# wiz55stm32.net
KiCad netlist of a schematic drawn in Altium Designer
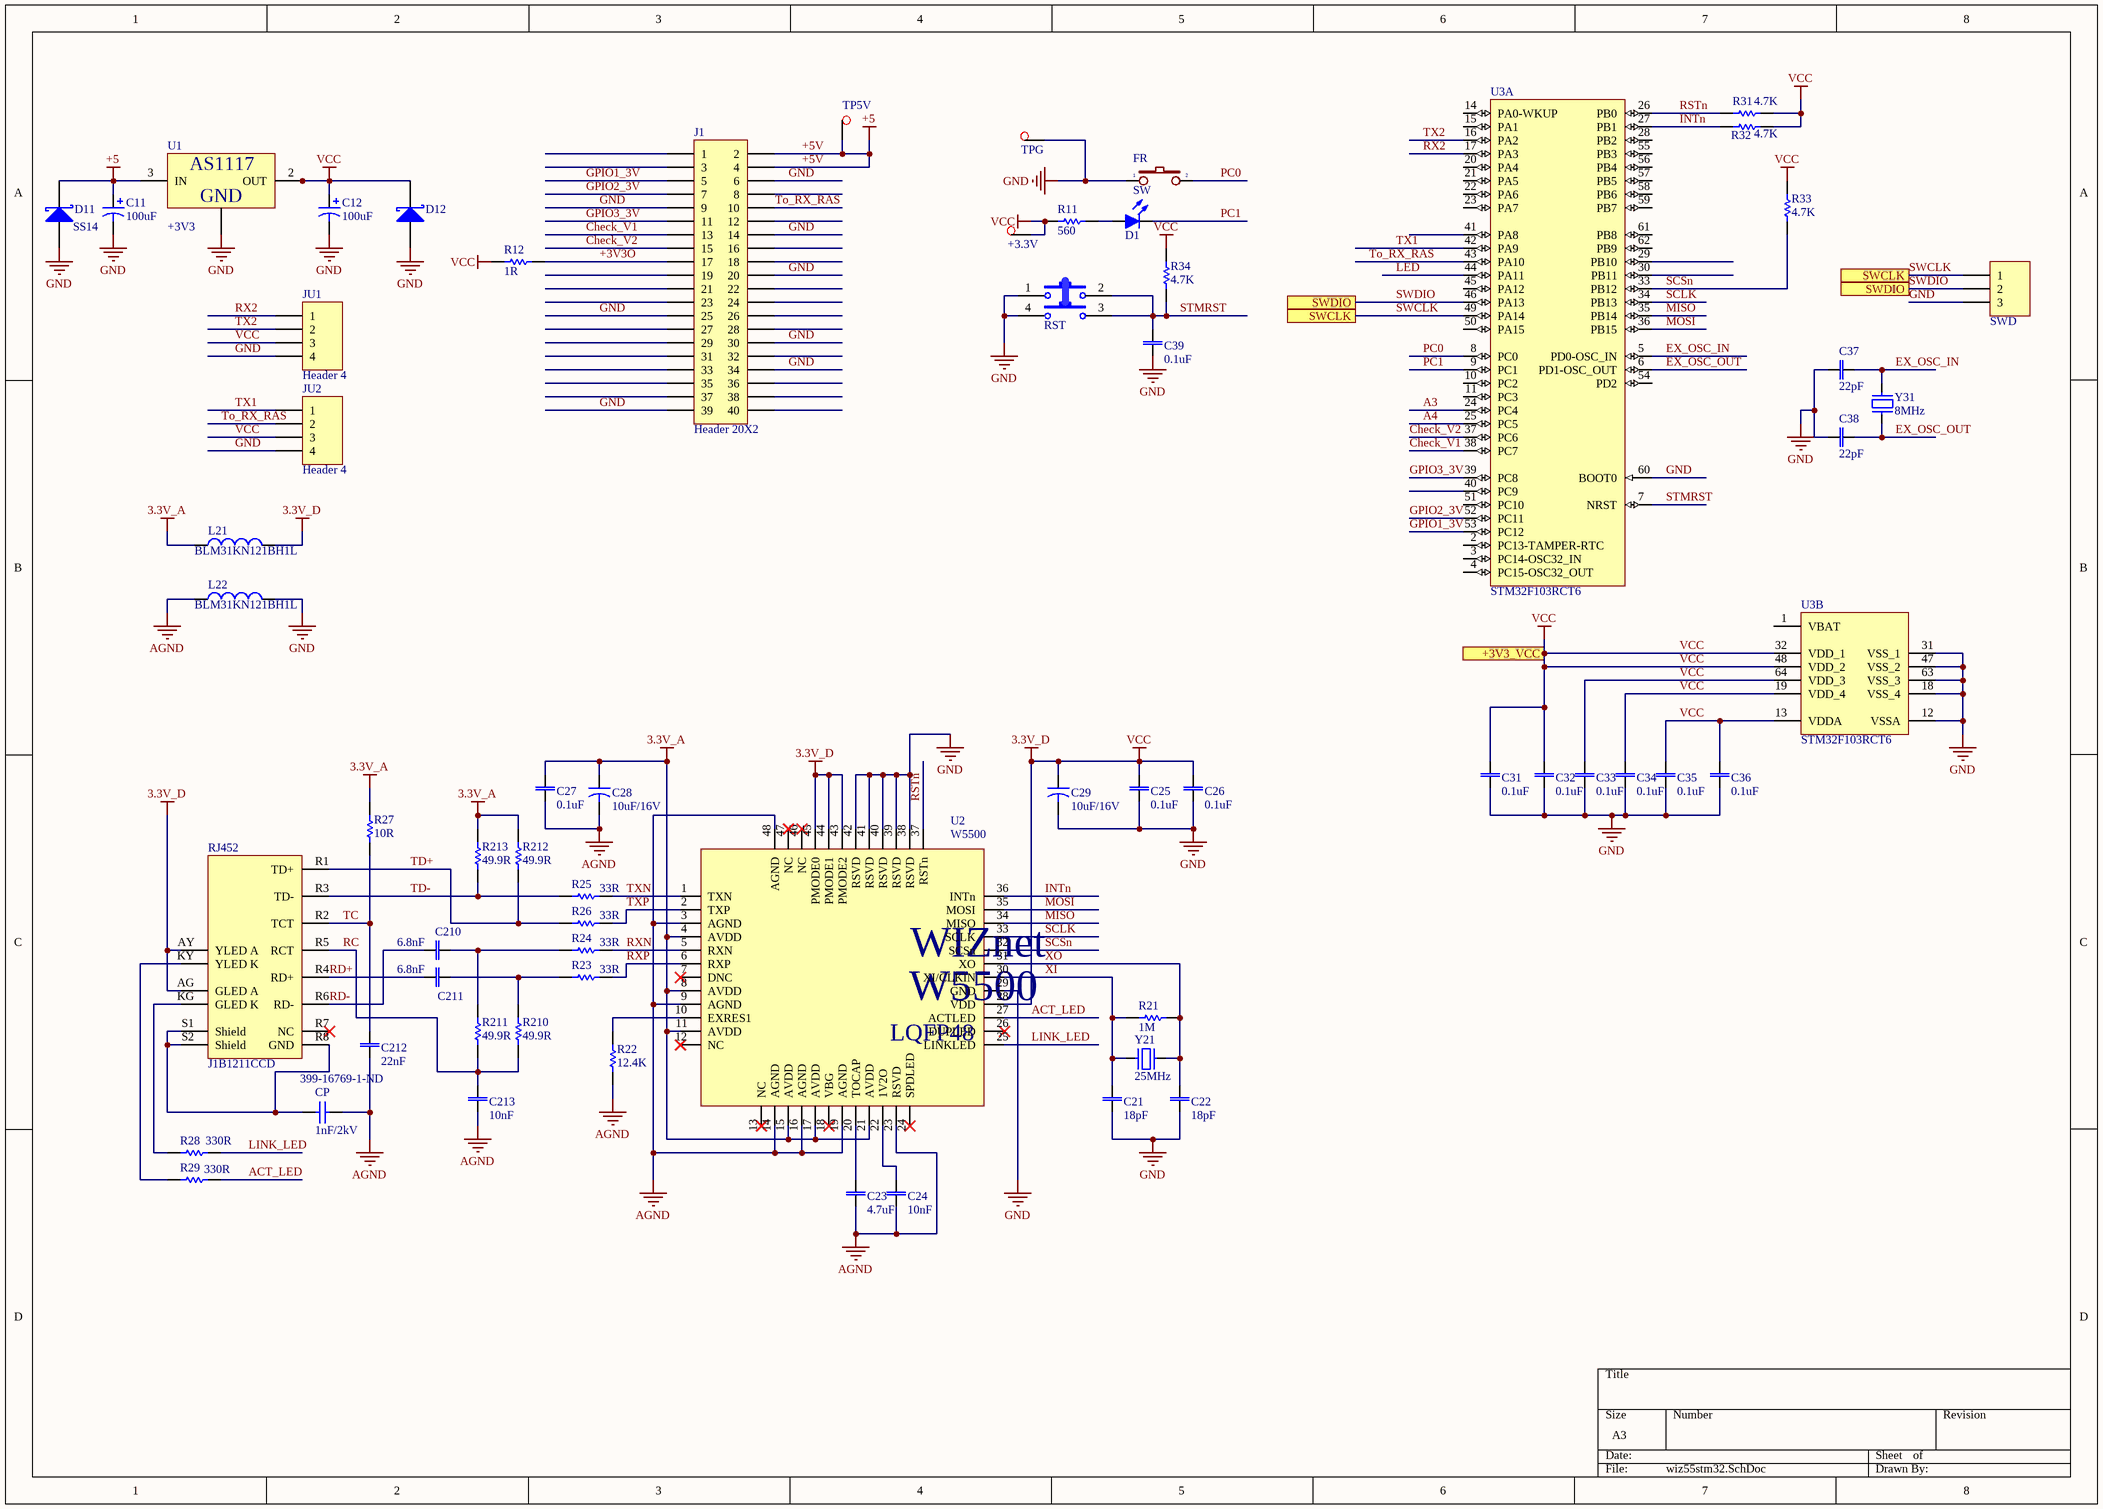
[diagram p0: wiz55stm32.SchDoc]

(export (version "E")
  (design (tool "Eeschema 10.0.6"))
  (components
    (comp (ref "+3.3V") (value "TP") (footprint "swatpcblib:TP2") (libsource (lib "swatpcblib") (part "TP")))
    (comp (ref "C11")
      (value "100uF")
      (footprint "CAP 3.8mm")
      (fields (field (name "Comment") "Cap"))
      (libsource (lib "swatpcblib") (part "Cap"))
    )
    (comp (ref "C12")
      (value "100uF")
      (footprint "CAP 3.8mm")
      (fields (field (name "Comment") "Cap"))
      (libsource (lib "swatpcblib") (part "Cap"))
    )
    (comp (ref "C21")
      (value "18pF")
      (footprint "swatpcblib:CAP 0805")
      (description "Capacitor non polarized")
      (fields (field (name "Comment") "Tụ điện dán 080518pF"))
      (libsource (lib "swatpcblib") (part "CAP NP"))
    )
    (comp (ref "C22")
      (value "18pF")
      (footprint "swatpcblib:CAP 0805")
      (description "Capacitor non polarized")
      (fields (field (name "Comment") "Tụ điện dán 080518pF"))
      (libsource (lib "swatpcblib") (part "CAP NP"))
    )
    (comp (ref "C23")
      (value "4.7uF")
      (footprint "swatpcblib:CAP 0805")
      (description "Capacitor non polarized")
      (fields (field (name "Comment") "Tụ điện dán 08054.7uF"))
      (libsource (lib "swatpcblib") (part "CAP NP"))
    )
    (comp (ref "C24")
      (value "10nF")
      (footprint "swatpcblib:CAP 0805")
      (description "Capacitor non polarized")
      (fields (field (name "Comment") "Tụ điện dán 080510nF"))
      (libsource (lib "swatpcblib") (part "CAP NP"))
    )
    (comp (ref "C25")
      (value "0.1uF")
      (footprint "swatpcblib:CAP 0805")
      (description "Capacitor non polarized")
      (fields (field (name "Comment") "Tụ điện dán 08050.1uF"))
      (libsource (lib "swatpcblib") (part "CAP NP"))
    )
    (comp (ref "C26")
      (value "0.1uF")
      (footprint "swatpcblib:CAP 0805")
      (description "Capacitor non polarized")
      (fields (field (name "Comment") "Tụ điện dán 08050.1uF"))
      (libsource (lib "swatpcblib") (part "CAP NP"))
    )
    (comp (ref "C27")
      (value "0.1uF")
      (footprint "swatpcblib:CAP 0805")
      (description "Capacitor non polarized")
      (fields (field (name "Comment") "Tụ điện dán 08050.1uF"))
      (libsource (lib "swatpcblib") (part "CAP NP"))
    )
    (comp (ref "C28")
      (value "10uF/16V")
      (footprint "CAP-A Size")
      (description "Tantla CAP A Size EIA/IECQ 3216")
      (libsource (lib "Scott_lib") (part "CAP-A Size"))
    )
    (comp (ref "C29")
      (value "10uF/16V")
      (footprint "CAP-A Size")
      (description "Tantla CAP A Size EIA/IECQ 3216")
      (libsource (lib "Scott_lib") (part "CAP-A Size"))
    )
    (comp (ref "C31")
      (value "0.1uF")
      (footprint "swatpcblib:CAP 0805")
      (description "Capacitor non polarized")
      (fields (field (name "Comment") "Tụ điện dán 08050.1uF"))
      (libsource (lib "swatpcblib") (part "CAP NP"))
    )
    (comp (ref "C32")
      (value "0.1uF")
      (footprint "swatpcblib:CAP 0805")
      (description "Capacitor non polarized")
      (fields (field (name "Comment") "Tụ điện dán 08050.1uF"))
      (libsource (lib "swatpcblib") (part "CAP NP"))
    )
    (comp (ref "C33")
      (value "0.1uF")
      (footprint "swatpcblib:CAP 0805")
      (description "Capacitor non polarized")
      (fields (field (name "Comment") "Tụ điện dán 08050.1uF"))
      (libsource (lib "swatpcblib") (part "CAP NP"))
    )
    (comp (ref "C34")
      (value "0.1uF")
      (footprint "swatpcblib:CAP 0805")
      (description "Capacitor non polarized")
      (fields (field (name "Comment") "Tụ điện dán 08050.1uF"))
      (libsource (lib "swatpcblib") (part "CAP NP"))
    )
    (comp (ref "C35")
      (value "0.1uF")
      (footprint "swatpcblib:CAP 0805")
      (description "Capacitor non polarized")
      (fields (field (name "Comment") "Tụ điện dán 08050.1uF"))
      (libsource (lib "swatpcblib") (part "CAP NP"))
    )
    (comp (ref "C36")
      (value "0.1uF")
      (footprint "swatpcblib:CAP 0805")
      (description "Capacitor non polarized")
      (fields (field (name "Comment") "Tụ điện dán 08050.1uF"))
      (libsource (lib "swatpcblib") (part "CAP NP"))
    )
    (comp (ref "C37")
      (value "22pF")
      (footprint "swatpcblib:CAP 0805")
      (description "Capacitor non polarized")
      (fields (field (name "Comment") "Tụ điện dán 080522pF"))
      (libsource (lib "swatpcblib") (part "CAP NP"))
    )
    (comp (ref "C38")
      (value "22pF")
      (footprint "swatpcblib:CAP 0805")
      (description "Capacitor non polarized")
      (fields (field (name "Comment") "Tụ điện dán 080522pF"))
      (libsource (lib "swatpcblib") (part "CAP NP"))
    )
    (comp (ref "C39")
      (value "0.1uF")
      (footprint "swatpcblib:CAP 0805")
      (description "Capacitor non polarized")
      (fields (field (name "Comment") "Tụ điện dán 08050.1uF"))
      (libsource (lib "swatpcblib") (part "CAP NP"))
    )
    (comp (ref "C210")
      (value "6.8nF")
      (footprint "swatpcblib:CAP 0805")
      (description "Capacitor non polarized")
      (fields (field (name "Comment") "Tụ điện dán 08056.8nF"))
      (libsource (lib "swatpcblib") (part "CAP NP"))
    )
    (comp (ref "C211")
      (value "6.8nF")
      (footprint "swatpcblib:CAP 0805")
      (description "Capacitor non polarized")
      (fields (field (name "Comment") "Tụ điện dán 08056.8nF"))
      (libsource (lib "swatpcblib") (part "CAP NP"))
    )
    (comp (ref "C212")
      (value "22nF")
      (footprint "swatpcblib:CAP 0805")
      (description "Capacitor non polarized")
      (fields (field (name "Comment") "Tụ điện dán 080522nF"))
      (libsource (lib "swatpcblib") (part "CAP NP"))
    )
    (comp (ref "C213")
      (value "10nF")
      (footprint "swatpcblib:CAP 0805")
      (description "Capacitor non polarized")
      (fields (field (name "Comment") "Tụ điện dán 080510nF"))
      (libsource (lib "swatpcblib") (part "CAP NP"))
    )
    (comp (ref "CP")
      (value "1nF/2kV")
      (footprint "CAP-1808")
      (description "Ceramic CAP 1808(4520)")
      (fields (field (name "SUPPLIER PART NUMBER 1") "399-16769-1-ND") (field (name "TOLERANCE") "20%"))
      (libsource (lib "Scott_lib") (part "CAP-1808"))
    )
    (comp (ref "D1") (value "Led") (footprint "LED 5mm Green") (libsource (lib "swatpcblib") (part "Led")))
    (comp (ref "D11")
      (value "SS14")
      (footprint "PBL - SMD Packages:DO-214AC")
      (description "Schottky Diodes Through Hole 3 A 40 V Schottky Diodes, DO-201AD, SB340 ,MBR340")
      (fields (field (name "Comment") "Đi ốt dánSS14"))
      (libsource (lib "swatpcblib") (part "Diodes Schottky"))
    )
    (comp (ref "D12")
      (value "Đi ốt dánPN:CPDH3V3UP")
      (footprint "swatpcblib:DO-35")
      (description "Zener 3.3V/1W")
      (libsource (lib "swatpcblib") (part "Diodes Schottky"))
    )
    (comp (ref "FR")
      (value "SW")
      (footprint "heromap:SW2-D1")
      (description "Switch button 2 pin")
      (libsource (lib "heromap") (part "SW2"))
    )
    (comp (ref "J1")
      (value "Header 20X2")
      (footprint "HDR2X20")
      (description "Header, 20-Pin, Dual row")
      (fields (field (name "PUBLISHER") "Altium Limited"))
      (libsource (lib "Miscellaneous Connectors") (part "Header 20X2"))
    )
    (comp (ref "JU1")
      (value "Header 4")
      (footprint "heromap:HDR1X4")
      (description "Header, 4-Pin")
      (fields (field (name "PUBLISHER") "Altium Limited"))
      (libsource (lib "heromap") (part "Header 4"))
    )
    (comp (ref "JU2")
      (value "Header 4")
      (footprint "heromap:HDR1X4")
      (description "Header, 4-Pin")
      (fields (field (name "PUBLISHER") "Altium Limited"))
      (libsource (lib "heromap") (part "Header 4"))
    )
    (comp (ref "L21")
      (value "BLM31KN121BH1L")
      (footprint "swatpcblib:SMD 1206")
      (description "Ferrite Beads 1206 120ohms 4A AEC-Q200")
      (libsource (lib "Scott_lib") (part "IND-0603"))
    )
    (comp (ref "L22")
      (value "BLM31KN121BH1L")
      (footprint "swatpcblib:SMD 1206")
      (description "Ferrite Beads 1206 120ohms 4A AEC-Q200")
      (libsource (lib "Scott_lib") (part "IND-0603"))
    )
    (comp (ref "R11")
      (value "560")
      (footprint "swatpcblib:RES 0805")
      (description "Resistor")
      (fields (field (name "Comment") "Điện trở dán 0603560"))
      (libsource (lib "swatpcblib") (part "Res"))
    )
    (comp (ref "R12")
      (value "1R")
      (footprint "swatpcblib:RES 0805")
      (description "Resistor")
      (fields (field (name "Comment") "Điện trở dán 08051R"))
      (libsource (lib "swatpcblib") (part "Res"))
    )
    (comp (ref "R21")
      (value "1M")
      (footprint "swatpcblib:RES 0805")
      (description "Resistor")
      (fields (field (name "Comment") "Điện trở dán 08051M"))
      (libsource (lib "swatpcblib") (part "Res"))
    )
    (comp (ref "R22")
      (value "12.4K")
      (footprint "swatpcblib:RES 0805")
      (description "Resistor")
      (fields (field (name "Comment") "Điện trở dán 080512.4K"))
      (libsource (lib "swatpcblib") (part "Res"))
    )
    (comp (ref "R23")
      (value "33R")
      (footprint "swatpcblib:RES 0805")
      (description "Resistor")
      (fields (field (name "Comment") "Điện trở dán 080533R"))
      (libsource (lib "swatpcblib") (part "Res"))
    )
    (comp (ref "R24")
      (value "33R")
      (footprint "swatpcblib:RES 0805")
      (description "Resistor")
      (fields (field (name "Comment") "Điện trở dán 080533R"))
      (libsource (lib "swatpcblib") (part "Res"))
    )
    (comp (ref "R25")
      (value "33R")
      (footprint "swatpcblib:RES 0805")
      (description "Resistor")
      (fields (field (name "Comment") "Điện trở dán 080533R"))
      (libsource (lib "swatpcblib") (part "Res"))
    )
    (comp (ref "R26")
      (value "33R")
      (footprint "swatpcblib:RES 0805")
      (description "Resistor")
      (fields (field (name "Comment") "Điện trở dán 080533R"))
      (libsource (lib "swatpcblib") (part "Res"))
    )
    (comp (ref "R27")
      (value "10R")
      (footprint "swatpcblib:RES 0805")
      (description "Resistor")
      (fields (field (name "Comment") "Điện trở dán 080510R"))
      (libsource (lib "swatpcblib") (part "Res"))
    )
    (comp (ref "R28")
      (value "330R")
      (footprint "swatpcblib:RES 0805")
      (description "Resistor")
      (fields (field (name "Comment") "Điện trở dán 0805330R"))
      (libsource (lib "swatpcblib") (part "Res"))
    )
    (comp (ref "R29")
      (value "330R")
      (footprint "swatpcblib:RES 0805")
      (description "Resistor")
      (fields (field (name "Comment") "Điện trở dán 0805330R"))
      (libsource (lib "swatpcblib") (part "Res"))
    )
    (comp (ref "R31")
      (value "4.7K")
      (footprint "swatpcblib:RES 0805")
      (description "Resistor")
      (fields (field (name "Comment") "Điện trở dán 08054.7K"))
      (libsource (lib "swatpcblib") (part "Res"))
    )
    (comp (ref "R32")
      (value "4.7K")
      (footprint "swatpcblib:RES 0805")
      (description "Resistor")
      (fields (field (name "Comment") "Điện trở dán 08054.7K"))
      (libsource (lib "swatpcblib") (part "Res"))
    )
    (comp (ref "R33")
      (value "4.7K")
      (footprint "swatpcblib:RES 0805")
      (description "Resistor")
      (fields (field (name "Comment") "Điện trở dán 08054.7K"))
      (libsource (lib "swatpcblib") (part "Res"))
    )
    (comp (ref "R34")
      (value "4.7K")
      (footprint "swatpcblib:RES 0805")
      (description "Resistor")
      (fields (field (name "Comment") "Điện trở dán 08054.7K"))
      (libsource (lib "swatpcblib") (part "Res"))
    )
    (comp (ref "R210")
      (value "49.9R")
      (footprint "swatpcblib:RES 0805")
      (description "Resistor")
      (fields (field (name "Comment") "Điện trở dán 080549.9R"))
      (libsource (lib "swatpcblib") (part "Res"))
    )
    (comp (ref "R211")
      (value "49.9R")
      (footprint "swatpcblib:RES 0805")
      (description "Resistor")
      (fields (field (name "Comment") "Điện trở dán 080549.9R"))
      (libsource (lib "swatpcblib") (part "Res"))
    )
    (comp (ref "R212")
      (value "49.9R")
      (footprint "swatpcblib:RES 0805")
      (description "Resistor")
      (fields (field (name "Comment") "Điện trở dán 080549.9R"))
      (libsource (lib "swatpcblib") (part "Res"))
    )
    (comp (ref "R213")
      (value "49.9R")
      (footprint "swatpcblib:RES 0805")
      (description "Resistor")
      (fields (field (name "Comment") "Điện trở dán 080549.9R"))
      (libsource (lib "swatpcblib") (part "Res"))
    )
    (comp (ref "RJ452")
      (value "J1B1211CCD")
      (footprint "swatpcblib:J1B1211CCD")
      (libsource (lib "WIZ850io_SCH_V100") (part "BS-R250210"))
    )
    (comp (ref "RST")
      (value "Nút bấm 4 chân cắm12x12x6mm")
      (footprint "SW")
      (libsource (lib "swatpcblib") (part "SW-4P-Small"))
    )
    (comp (ref "SWD")
      (value "Header 3")
      (footprint "heromap:HDR1X3")
      (description "Header, 3-Pin")
      (fields (field (name "PUBLISHER") "Altium Limited"))
      (libsource (lib "heromap") (part "Header 3"))
    )
    (comp (ref "TP5V") (value "TP") (footprint "swatpcblib:TP2") (libsource (lib "swatpcblib") (part "TP")))
    (comp (ref "TPG") (value "TP") (footprint "swatpcblib:TP2") (libsource (lib "swatpcblib") (part "TP")))
    (comp (ref "U1")
      (value "IC nguồn AS1117 dán+3V3")
      (footprint "SOT223-4N")
      (fields (field (name "VL") "+3V3"))
      (libsource (lib "swatpcblib") (part "AS1117"))
    )
    (comp (ref "U2")
      (value "W5500")
      (footprint "swatpcblib:WIZNET W5500")
      (description "WIZnet W5500")
      (libsource (lib "WIZnet Open-source Hardware Library V1.0") (part "W5500"))
    )
    (comp (ref "U3")
      (value "STM32F103RCT6")
      (footprint "LQFP64_Tuan")
      (libsource (lib "STMicroelectronics STM32 F1") (part "STM32F103RCT6"))
    )
    (comp (ref "Y21") (value "25MHz") (footprint "XT2") (libsource (lib "swatpcblib") (part "Crystal")))
    (comp (ref "Y31") (value "8MHz") (footprint "XT2") (libsource (lib "Tuan") (part "Crystal")))
  )
  (nets
    (net (code "1") (name "+5") (class "Default")
      (node (ref "C11") (pin "1") (pinfunction "1_1") (pintype "passive"))
      (node (ref "D11") (pin "K") (pinfunction "K_K") (pintype "passive"))
      (node (ref "J1") (pin "2") (pinfunction "2_2") (pintype "passive"))
      (node (ref "J1") (pin "4") (pinfunction "4_4") (pintype "passive"))
      (node (ref "TP5V") (pin "1") (pinfunction "1_1") (pintype "passive"))
      (node (ref "U1") (pin "3") (pinfunction "IN_3") (pintype "power_in"))
    )
    (net (code "2") (name "/+3V3O") (class "Default")
      (node (ref "J1") (pin "17") (pinfunction "17_17") (pintype "passive"))
      (node (ref "R12") (pin "2") (pinfunction "2_2") (pintype "passive"))
    )
    (net (code "3") (name "/A3") (class "Default")
      (node (ref "U3") (pin "24") (pinfunction "PC4_24") (pintype "bidirectional"))
    )
    (net (code "4") (name "/A4") (class "Default")
      (node (ref "U3") (pin "25") (pinfunction "PC5_25") (pintype "bidirectional"))
    )
    (net (code "5") (name "/ACT_LED") (class "Default")
      (node (ref "R29") (pin "2") (pinfunction "2_2") (pintype "passive"))
      (node (ref "U2") (pin "27") (pinfunction "ACTLED_27") (pintype "passive"))
    )
    (net (code "6") (name "/Check_V1") (class "Default")
      (node (ref "J1") (pin "13") (pinfunction "13_13") (pintype "passive"))
      (node (ref "U3") (pin "38") (pinfunction "PC7_38") (pintype "bidirectional"))
    )
    (net (code "7") (name "/Check_V2") (class "Default")
      (node (ref "J1") (pin "15") (pinfunction "15_15") (pintype "passive"))
      (node (ref "U3") (pin "37") (pinfunction "PC6_37") (pintype "bidirectional"))
    )
    (net (code "8") (name "/EX_OSC_IN") (class "Default")
      (node (ref "C37") (pin "1") (pinfunction "1_1") (pintype "passive"))
      (node (ref "U3") (pin "5") (pinfunction "PD0-OSC_IN_5") (pintype "bidirectional"))
      (node (ref "Y31") (pin "2") (pinfunction "2_2") (pintype "passive"))
    )
    (net (code "9") (name "/EX_OSC_OUT") (class "Default")
      (node (ref "C38") (pin "1") (pinfunction "1_1") (pintype "passive"))
      (node (ref "U3") (pin "6") (pinfunction "PD1-OSC_OUT_6") (pintype "bidirectional"))
      (node (ref "Y31") (pin "1") (pinfunction "1_1") (pintype "passive"))
    )
    (net (code "10") (name "/GPIO1_3V") (class "Default")
      (node (ref "J1") (pin "5") (pinfunction "5_5") (pintype "passive"))
      (node (ref "U3") (pin "53") (pinfunction "PC12_53") (pintype "bidirectional"))
    )
    (net (code "11") (name "/GPIO2_3V") (class "Default")
      (node (ref "J1") (pin "7") (pinfunction "7_7") (pintype "passive"))
      (node (ref "U3") (pin "52") (pinfunction "PC11_52") (pintype "bidirectional"))
    )
    (net (code "12") (name "/GPIO3_3V") (class "Default")
      (node (ref "J1") (pin "11") (pinfunction "11_11") (pintype "passive"))
      (node (ref "U3") (pin "39") (pinfunction "PC8_39") (pintype "bidirectional"))
    )
    (net (code "13") (name "/INTn") (class "Default")
      (node (ref "R32") (pin "2") (pinfunction "2_2") (pintype "passive"))
      (node (ref "U2") (pin "36") (pinfunction "INTn_36") (pintype "passive"))
      (node (ref "U3") (pin "27") (pinfunction "PB1_27") (pintype "bidirectional"))
    )
    (net (code "14") (name "/LED") (class "Default")
      (node (ref "U3") (pin "44") (pinfunction "PA11_44") (pintype "bidirectional"))
    )
    (net (code "15") (name "/LINK_LED") (class "Default")
      (node (ref "R28") (pin "2") (pinfunction "2_2") (pintype "passive"))
      (node (ref "U2") (pin "25") (pinfunction "LINKLED_25") (pintype "passive"))
    )
    (net (code "16") (name "/MISO") (class "Default")
      (node (ref "U2") (pin "34") (pinfunction "MISO_34") (pintype "passive"))
      (node (ref "U3") (pin "35") (pinfunction "PB14_35") (pintype "bidirectional"))
    )
    (net (code "17") (name "/MOSI") (class "Default")
      (node (ref "U2") (pin "35") (pinfunction "MOSI_35") (pintype "passive"))
      (node (ref "U3") (pin "36") (pinfunction "PB15_36") (pintype "bidirectional"))
    )
    (net (code "18") (name "/PC0") (class "Default")
      (node (ref "FR") (pin "2") (pinfunction "2_2") (pintype "passive"))
      (node (ref "U3") (pin "8") (pinfunction "PC0_8") (pintype "bidirectional"))
    )
    (net (code "19") (name "/PC1") (class "Default")
      (node (ref "D1") (pin "K") (pinfunction "K_K") (pintype "passive"))
      (node (ref "U3") (pin "9") (pinfunction "PC1_9") (pintype "bidirectional"))
    )
    (net (code "20") (name "/RC") (class "Default")
      (node (ref "C213") (pin "1") (pinfunction "1_1") (pintype "passive"))
      (node (ref "R210") (pin "1") (pinfunction "1_1") (pintype "passive"))
      (node (ref "R211") (pin "1") (pinfunction "1_1") (pintype "passive"))
      (node (ref "RJ452") (pin "R5") (pinfunction "RCT_R5") (pintype "passive"))
    )
    (net (code "21") (name "/RD+") (class "Default")
      (node (ref "C211") (pin "2") (pinfunction "2_2") (pintype "passive"))
      (node (ref "RJ452") (pin "R4") (pinfunction "RD+_R4") (pintype "passive"))
    )
    (net (code "22") (name "/RD-") (class "Default")
      (node (ref "C210") (pin "2") (pinfunction "2_2") (pintype "passive"))
      (node (ref "RJ452") (pin "R6") (pinfunction "RD-_R6") (pintype "passive"))
    )
    (net (code "23") (name "/RSTn") (class "Default")
      (node (ref "R31") (pin "2") (pinfunction "2_2") (pintype "passive"))
      (node (ref "U2") (pin "37") (pinfunction "RSTn_37") (pintype "passive"))
      (node (ref "U3") (pin "26") (pinfunction "PB0_26") (pintype "bidirectional"))
    )
    (net (code "24") (name "/RX2") (class "Default")
      (node (ref "JU1") (pin "1") (pinfunction "1_1") (pintype "passive"))
      (node (ref "U3") (pin "17") (pinfunction "PA3_17") (pintype "bidirectional"))
    )
    (net (code "25") (name "/RXN") (class "Default")
      (node (ref "R24") (pin "1") (pinfunction "1_1") (pintype "passive"))
      (node (ref "U2") (pin "5") (pinfunction "RXN_5") (pintype "passive"))
    )
    (net (code "26") (name "/RXP") (class "Default")
      (node (ref "R23") (pin "1") (pinfunction "1_1") (pintype "passive"))
      (node (ref "U2") (pin "6") (pinfunction "RXP_6") (pintype "passive"))
    )
    (net (code "27") (name "/SCLK") (class "Default")
      (node (ref "U2") (pin "33") (pinfunction "SCLK_33") (pintype "passive"))
      (node (ref "U3") (pin "34") (pinfunction "PB13_34") (pintype "bidirectional"))
    )
    (net (code "28") (name "/SCSn") (class "Default")
      (node (ref "R33") (pin "1") (pinfunction "1_1") (pintype "passive"))
      (node (ref "U2") (pin "32") (pinfunction "SCSn_32") (pintype "passive"))
      (node (ref "U3") (pin "33") (pinfunction "PB12_33") (pintype "bidirectional"))
    )
    (net (code "29") (name "/STMRST") (class "Default")
      (node (ref "C39") (pin "2") (pinfunction "2_2") (pintype "passive"))
      (node (ref "R34") (pin "1") (pinfunction "1_1") (pintype "passive"))
      (node (ref "RST") (pin "2") (pinfunction "2_2") (pintype "passive"))
      (node (ref "RST") (pin "3") (pinfunction "3_3") (pintype "passive"))
      (node (ref "U3") (pin "7") (pinfunction "NRST_7") (pintype "bidirectional"))
    )
    (net (code "30") (name "/SWCLK") (class "Default")
      (node (ref "SWD") (pin "1") (pinfunction "1_1") (pintype "passive"))
      (node (ref "U3") (pin "49") (pinfunction "PA14_49") (pintype "bidirectional"))
    )
    (net (code "31") (name "/SWDIO") (class "Default")
      (node (ref "SWD") (pin "2") (pinfunction "2_2") (pintype "passive"))
      (node (ref "U3") (pin "46") (pinfunction "PA13_46") (pintype "bidirectional"))
    )
    (net (code "32") (name "/TC") (class "Default")
      (node (ref "C212") (pin "1") (pinfunction "1_1") (pintype "passive"))
      (node (ref "R27") (pin "2") (pinfunction "2_2") (pintype "passive"))
      (node (ref "RJ452") (pin "R2") (pinfunction "TCT_R2") (pintype "passive"))
    )
    (net (code "33") (name "/TD+") (class "Default")
      (node (ref "R212") (pin "1") (pinfunction "1_1") (pintype "passive"))
      (node (ref "R26") (pin "2") (pinfunction "2_2") (pintype "passive"))
      (node (ref "RJ452") (pin "R1") (pinfunction "TD+_R1") (pintype "passive"))
    )
    (net (code "34") (name "/TD-") (class "Default")
      (node (ref "R213") (pin "1") (pinfunction "1_1") (pintype "passive"))
      (node (ref "R25") (pin "2") (pinfunction "2_2") (pintype "passive"))
      (node (ref "RJ452") (pin "R3") (pinfunction "TD-_R3") (pintype "passive"))
    )
    (net (code "35") (name "/TX1") (class "Default")
      (node (ref "JU2") (pin "1") (pinfunction "1_1") (pintype "passive"))
      (node (ref "U3") (pin "42") (pinfunction "PA9_42") (pintype "bidirectional"))
    )
    (net (code "36") (name "/TX2") (class "Default")
      (node (ref "JU1") (pin "2") (pinfunction "2_2") (pintype "passive"))
      (node (ref "U3") (pin "16") (pinfunction "PA2_16") (pintype "bidirectional"))
    )
    (net (code "37") (name "/TXN") (class "Default")
      (node (ref "R25") (pin "1") (pinfunction "1_1") (pintype "passive"))
      (node (ref "U2") (pin "1") (pinfunction "TXN_1") (pintype "passive"))
    )
    (net (code "38") (name "/TXP") (class "Default")
      (node (ref "R26") (pin "1") (pinfunction "1_1") (pintype "passive"))
      (node (ref "U2") (pin "2") (pinfunction "TXP_2") (pintype "passive"))
    )
    (net (code "39") (name "/To_RX_RAS") (class "Default")
      (node (ref "J1") (pin "10") (pinfunction "10_10") (pintype "passive"))
      (node (ref "JU2") (pin "2") (pinfunction "2_2") (pintype "passive"))
      (node (ref "U3") (pin "43") (pinfunction "PA10_43") (pintype "bidirectional"))
    )
    (net (code "40") (name "/XI") (class "Default")
      (node (ref "C21") (pin "2") (pinfunction "2_2") (pintype "passive"))
      (node (ref "R21") (pin "1") (pinfunction "1_1") (pintype "passive"))
      (node (ref "U2") (pin "30") (pinfunction "XI/CLKIN_30") (pintype "passive"))
      (node (ref "Y21") (pin "1") (pinfunction "1_1") (pintype "passive"))
    )
    (net (code "41") (name "/XO") (class "Default")
      (node (ref "C22") (pin "2") (pinfunction "2_2") (pintype "passive"))
      (node (ref "R21") (pin "2") (pinfunction "2_2") (pintype "passive"))
      (node (ref "U2") (pin "31") (pinfunction "XO_31") (pintype "passive"))
      (node (ref "Y21") (pin "2") (pinfunction "2_2") (pintype "passive"))
    )
    (net (code "42") (name "3.3V_A") (class "Default")
      (node (ref "C27") (pin "2") (pinfunction "2_2") (pintype "passive"))
      (node (ref "C28") (pin "1") (pinfunction "1_1") (pintype "passive"))
      (node (ref "L21") (pin "1") (pinfunction "1_1") (pintype "passive"))
      (node (ref "R212") (pin "2") (pinfunction "2_2") (pintype "passive"))
      (node (ref "R213") (pin "2") (pinfunction "2_2") (pintype "passive"))
      (node (ref "R27") (pin "1") (pinfunction "1_1") (pintype "passive"))
      (node (ref "U2") (pin "11") (pinfunction "AVDD_11") (pintype "passive"))
      (node (ref "U2") (pin "15") (pinfunction "AVDD_15") (pintype "passive"))
      (node (ref "U2") (pin "17") (pinfunction "AVDD_17") (pintype "passive"))
      (node (ref "U2") (pin "21") (pinfunction "AVDD_21") (pintype "passive"))
      (node (ref "U2") (pin "4") (pinfunction "AVDD_4") (pintype "passive"))
      (node (ref "U2") (pin "8") (pinfunction "AVDD_8") (pintype "passive"))
    )
    (net (code "43") (name "3.3V_D") (class "Default")
      (node (ref "+3.3V") (pin "1") (pinfunction "1_1") (pintype "passive"))
      (node (ref "C12") (pin "1") (pinfunction "1_1") (pintype "passive"))
      (node (ref "C25") (pin "2") (pinfunction "2_2") (pintype "passive"))
      (node (ref "C26") (pin "2") (pinfunction "2_2") (pintype "passive"))
      (node (ref "C29") (pin "1") (pinfunction "1_1") (pintype "passive"))
      (node (ref "C31") (pin "2") (pinfunction "2_2") (pintype "passive"))
      (node (ref "C32") (pin "2") (pinfunction "2_2") (pintype "passive"))
      (node (ref "C33") (pin "2") (pinfunction "2_2") (pintype "passive"))
      (node (ref "C34") (pin "2") (pinfunction "2_2") (pintype "passive"))
      (node (ref "C35") (pin "2") (pinfunction "2_2") (pintype "passive"))
      (node (ref "C36") (pin "2") (pinfunction "2_2") (pintype "passive"))
      (node (ref "D12") (pin "K") (pinfunction "K_K") (pintype "passive"))
      (node (ref "JU1") (pin "3") (pinfunction "3_3") (pintype "passive"))
      (node (ref "JU2") (pin "3") (pinfunction "3_3") (pintype "passive"))
      (node (ref "L21") (pin "2") (pinfunction "2_2") (pintype "passive"))
      (node (ref "R11") (pin "1") (pinfunction "1_1") (pintype "passive"))
      (node (ref "R12") (pin "1") (pinfunction "1_1") (pintype "passive"))
      (node (ref "R31") (pin "1") (pinfunction "1_1") (pintype "passive"))
      (node (ref "R32") (pin "1") (pinfunction "1_1") (pintype "passive"))
      (node (ref "R33") (pin "2") (pinfunction "2_2") (pintype "passive"))
      (node (ref "R34") (pin "2") (pinfunction "2_2") (pintype "passive"))
      (node (ref "RJ452") (pin "AG") (pinfunction "GLED_A_AG") (pintype "passive"))
      (node (ref "RJ452") (pin "AY") (pinfunction "YLED_A_AY") (pintype "passive"))
      (node (ref "U1") (pin "2") (pinfunction "OUT_2") (pintype "power_in"))
      (node (ref "U1") (pin "4") (pinfunction "4_4") (pintype "passive"))
      (node (ref "U2") (pin "28") (pinfunction "VDD_28") (pintype "passive"))
      (node (ref "U2") (pin "43") (pinfunction "PMODE2_43") (pintype "passive"))
      (node (ref "U2") (pin "44") (pinfunction "PMODE1_44") (pintype "passive"))
      (node (ref "U2") (pin "45") (pinfunction "PMODE0_45") (pintype "passive"))
      (node (ref "U3") (pin "13") (pinfunction "VDDA_13") (pintype "power_in"))
      (node (ref "U3") (pin "19") (pinfunction "VDD_4_19") (pintype "power_in"))
      (node (ref "U3") (pin "32") (pinfunction "VDD_1_32") (pintype "power_in"))
      (node (ref "U3") (pin "48") (pinfunction "VDD_2_48") (pintype "power_in"))
      (node (ref "U3") (pin "64") (pinfunction "VDD_3_64") (pintype "power_in"))
    )
    (net (code "44") (name "AGND") (class "Default")
      (node (ref "C212") (pin "2") (pinfunction "2_2") (pintype "passive"))
      (node (ref "C213") (pin "2") (pinfunction "2_2") (pintype "passive"))
      (node (ref "C23") (pin "1") (pinfunction "1_1") (pintype "passive"))
      (node (ref "C24") (pin "1") (pinfunction "1_1") (pintype "passive"))
      (node (ref "C27") (pin "1") (pinfunction "1_1") (pintype "passive"))
      (node (ref "C28") (pin "2") (pinfunction "2_2") (pintype "passive"))
      (node (ref "CP") (pin "1") (pinfunction "1_1") (pintype "passive"))
      (node (ref "L22") (pin "1") (pinfunction "1_1") (pintype "passive"))
      (node (ref "R22") (pin "1") (pinfunction "1_1") (pintype "passive"))
      (node (ref "U2") (pin "14") (pinfunction "AGND_14") (pintype "passive"))
      (node (ref "U2") (pin "16") (pinfunction "AGND_16") (pintype "passive"))
      (node (ref "U2") (pin "19") (pinfunction "AGND_19") (pintype "passive"))
      (node (ref "U2") (pin "23") (pinfunction "RSVD_23") (pintype "passive"))
      (node (ref "U2") (pin "3") (pinfunction "AGND_3") (pintype "passive"))
      (node (ref "U2") (pin "48") (pinfunction "AGND_48") (pintype "passive"))
      (node (ref "U2") (pin "9") (pinfunction "AGND_9") (pintype "passive"))
    )
    (net (code "45") (name "GND") (class "Default")
      (node (ref "C11") (pin "2") (pinfunction "2_2") (pintype "passive"))
      (node (ref "C12") (pin "2") (pinfunction "2_2") (pintype "passive"))
      (node (ref "C21") (pin "1") (pinfunction "1_1") (pintype "passive"))
      (node (ref "C22") (pin "1") (pinfunction "1_1") (pintype "passive"))
      (node (ref "C25") (pin "1") (pinfunction "1_1") (pintype "passive"))
      (node (ref "C26") (pin "1") (pinfunction "1_1") (pintype "passive"))
      (node (ref "C29") (pin "2") (pinfunction "2_2") (pintype "passive"))
      (node (ref "C31") (pin "1") (pinfunction "1_1") (pintype "passive"))
      (node (ref "C32") (pin "1") (pinfunction "1_1") (pintype "passive"))
      (node (ref "C33") (pin "1") (pinfunction "1_1") (pintype "passive"))
      (node (ref "C34") (pin "1") (pinfunction "1_1") (pintype "passive"))
      (node (ref "C35") (pin "1") (pinfunction "1_1") (pintype "passive"))
      (node (ref "C36") (pin "1") (pinfunction "1_1") (pintype "passive"))
      (node (ref "C37") (pin "2") (pinfunction "2_2") (pintype "passive"))
      (node (ref "C38") (pin "2") (pinfunction "2_2") (pintype "passive"))
      (node (ref "C39") (pin "1") (pinfunction "1_1") (pintype "passive"))
      (node (ref "D11") (pin "A") (pinfunction "A_A") (pintype "passive"))
      (node (ref "D12") (pin "A") (pinfunction "A_A") (pintype "passive"))
      (node (ref "FR") (pin "1") (pinfunction "1_1") (pintype "passive"))
      (node (ref "J1") (pin "14") (pinfunction "14_14") (pintype "passive"))
      (node (ref "J1") (pin "20") (pinfunction "20_20") (pintype "passive"))
      (node (ref "J1") (pin "25") (pinfunction "25_25") (pintype "passive"))
      (node (ref "J1") (pin "30") (pinfunction "30_30") (pintype "passive"))
      (node (ref "J1") (pin "34") (pinfunction "34_34") (pintype "passive"))
      (node (ref "J1") (pin "39") (pinfunction "39_39") (pintype "passive"))
      (node (ref "J1") (pin "6") (pinfunction "6_6") (pintype "passive"))
      (node (ref "J1") (pin "9") (pinfunction "9_9") (pintype "passive"))
      (node (ref "JU1") (pin "4") (pinfunction "4_4") (pintype "passive"))
      (node (ref "JU2") (pin "4") (pinfunction "4_4") (pintype "passive"))
      (node (ref "L22") (pin "2") (pinfunction "2_2") (pintype "passive"))
      (node (ref "RST") (pin "1") (pinfunction "1_1") (pintype "passive"))
      (node (ref "RST") (pin "4") (pinfunction "4_4") (pintype "passive"))
      (node (ref "SWD") (pin "3") (pinfunction "3_3") (pintype "passive"))
      (node (ref "TPG") (pin "1") (pinfunction "1_1") (pintype "passive"))
      (node (ref "U1") (pin "1") (pinfunction "GND_1") (pintype "power_in"))
      (node (ref "U2") (pin "29") (pinfunction "GND_29") (pintype "passive"))
      (node (ref "U2") (pin "38") (pinfunction "RSVD_38") (pintype "passive"))
      (node (ref "U2") (pin "39") (pinfunction "RSVD_39") (pintype "passive"))
      (node (ref "U2") (pin "40") (pinfunction "RSVD_40") (pintype "passive"))
      (node (ref "U2") (pin "41") (pinfunction "RSVD_41") (pintype "passive"))
      (node (ref "U2") (pin "42") (pinfunction "RSVD_42") (pintype "passive"))
      (node (ref "U3") (pin "12") (pinfunction "VSSA_12") (pintype "power_in"))
      (node (ref "U3") (pin "18") (pinfunction "VSS_4_18") (pintype "power_in"))
      (node (ref "U3") (pin "31") (pinfunction "VSS_1_31") (pintype "power_in"))
      (node (ref "U3") (pin "47") (pinfunction "VSS_2_47") (pintype "power_in"))
      (node (ref "U3") (pin "60") (pinfunction "BOOT0_60") (pintype "input"))
      (node (ref "U3") (pin "63") (pinfunction "VSS_3_63") (pintype "power_in"))
    )
    (net (code "46") (name "Net-(C210-Pad1)") (class "Default")
      (node (ref "C210") (pin "1") (pinfunction "1_1") (pintype "passive"))
      (node (ref "R211") (pin "2") (pinfunction "2_2") (pintype "passive"))
      (node (ref "R24") (pin "2") (pinfunction "2_2") (pintype "passive"))
    )
    (net (code "47") (name "Net-(C211-Pad1)") (class "Default")
      (node (ref "C211") (pin "1") (pinfunction "1_1") (pintype "passive"))
      (node (ref "R210") (pin "2") (pinfunction "2_2") (pintype "passive"))
      (node (ref "R23") (pin "2") (pinfunction "2_2") (pintype "passive"))
    )
    (net (code "48") (name "Net-(D1-PadA)") (class "Default")
      (node (ref "D1") (pin "A") (pinfunction "A_A") (pintype "passive"))
      (node (ref "R11") (pin "2") (pinfunction "2_2") (pintype "passive"))
    )
    (net (code "49") (name "Net-(RJ452-GLED_K)") (class "Default")
      (node (ref "R28") (pin "1") (pinfunction "1_1") (pintype "passive"))
      (node (ref "RJ452") (pin "KG") (pinfunction "GLED_K_KG") (pintype "passive"))
    )
    (net (code "50") (name "Net-(RJ452-GND)") (class "Default")
      (node (ref "CP") (pin "2") (pinfunction "2_2") (pintype "passive"))
      (node (ref "RJ452") (pin "R8") (pinfunction "GND_R8") (pintype "passive"))
      (node (ref "RJ452") (pin "S1") (pinfunction "Shield_S1") (pintype "passive"))
      (node (ref "RJ452") (pin "S2") (pinfunction "Shield_S2") (pintype "passive"))
    )
    (net (code "51") (name "Net-(RJ452-YLED_K)") (class "Default")
      (node (ref "R29") (pin "1") (pinfunction "1_1") (pintype "passive"))
      (node (ref "RJ452") (pin "KY") (pinfunction "YLED_K_KY") (pintype "passive"))
    )
    (net (code "52") (name "Net-(U2-1V2O)") (class "Default")
      (node (ref "C24") (pin "2") (pinfunction "2_2") (pintype "passive"))
      (node (ref "U2") (pin "22") (pinfunction "1V2O_22") (pintype "passive"))
    )
    (net (code "53") (name "Net-(U2-EXRES1)") (class "Default")
      (node (ref "R22") (pin "2") (pinfunction "2_2") (pintype "passive"))
      (node (ref "U2") (pin "10") (pinfunction "EXRES1_10") (pintype "passive"))
    )
    (net (code "54") (name "Net-(U2-TOCAP)") (class "Default")
      (node (ref "C23") (pin "2") (pinfunction "2_2") (pintype "passive"))
      (node (ref "U2") (pin "20") (pinfunction "TOCAP_20") (pintype "passive"))
    )
    (net (code "55") (name "unconnected-(J1-Pad1)") (class "Default")
      (node (ref "J1") (pin "1") (pinfunction "1_1") (pintype "passive"))
    )
    (net (code "56") (name "unconnected-(J1-Pad3)") (class "Default")
      (node (ref "J1") (pin "3") (pinfunction "3_3") (pintype "passive"))
    )
    (net (code "57") (name "unconnected-(J1-Pad8)") (class "Default")
      (node (ref "J1") (pin "8") (pinfunction "8_8") (pintype "passive"))
    )
    (net (code "58") (name "unconnected-(J1-Pad12)") (class "Default")
      (node (ref "J1") (pin "12") (pinfunction "12_12") (pintype "passive"))
    )
    (net (code "59") (name "unconnected-(J1-Pad16)") (class "Default")
      (node (ref "J1") (pin "16") (pinfunction "16_16") (pintype "passive"))
    )
    (net (code "60") (name "unconnected-(J1-Pad18)") (class "Default")
      (node (ref "J1") (pin "18") (pinfunction "18_18") (pintype "passive"))
    )
    (net (code "61") (name "unconnected-(J1-Pad19)") (class "Default")
      (node (ref "J1") (pin "19") (pinfunction "19_19") (pintype "passive"))
    )
    (net (code "62") (name "unconnected-(J1-Pad21)") (class "Default")
      (node (ref "J1") (pin "21") (pinfunction "21_21") (pintype "passive"))
    )
    (net (code "63") (name "unconnected-(J1-Pad22)") (class "Default")
      (node (ref "J1") (pin "22") (pinfunction "22_22") (pintype "passive"))
    )
    (net (code "64") (name "unconnected-(J1-Pad23)") (class "Default")
      (node (ref "J1") (pin "23") (pinfunction "23_23") (pintype "passive"))
    )
    (net (code "65") (name "unconnected-(J1-Pad24)") (class "Default")
      (node (ref "J1") (pin "24") (pinfunction "24_24") (pintype "passive"))
    )
    (net (code "66") (name "unconnected-(J1-Pad26)") (class "Default")
      (node (ref "J1") (pin "26") (pinfunction "26_26") (pintype "passive"))
    )
    (net (code "67") (name "unconnected-(J1-Pad27)") (class "Default")
      (node (ref "J1") (pin "27") (pinfunction "27_27") (pintype "passive"))
    )
    (net (code "68") (name "unconnected-(J1-Pad28)") (class "Default")
      (node (ref "J1") (pin "28") (pinfunction "28_28") (pintype "passive"))
    )
    (net (code "69") (name "unconnected-(J1-Pad29)") (class "Default")
      (node (ref "J1") (pin "29") (pinfunction "29_29") (pintype "passive"))
    )
    (net (code "70") (name "unconnected-(J1-Pad31)") (class "Default")
      (node (ref "J1") (pin "31") (pinfunction "31_31") (pintype "passive"))
    )
    (net (code "71") (name "unconnected-(J1-Pad32)") (class "Default")
      (node (ref "J1") (pin "32") (pinfunction "32_32") (pintype "passive"))
    )
    (net (code "72") (name "unconnected-(J1-Pad33)") (class "Default")
      (node (ref "J1") (pin "33") (pinfunction "33_33") (pintype "passive"))
    )
    (net (code "73") (name "unconnected-(J1-Pad35)") (class "Default")
      (node (ref "J1") (pin "35") (pinfunction "35_35") (pintype "passive"))
    )
    (net (code "74") (name "unconnected-(J1-Pad36)") (class "Default")
      (node (ref "J1") (pin "36") (pinfunction "36_36") (pintype "passive"))
    )
    (net (code "75") (name "unconnected-(J1-Pad37)") (class "Default")
      (node (ref "J1") (pin "37") (pinfunction "37_37") (pintype "passive"))
    )
    (net (code "76") (name "unconnected-(J1-Pad38)") (class "Default")
      (node (ref "J1") (pin "38") (pinfunction "38_38") (pintype "passive"))
    )
    (net (code "77") (name "unconnected-(J1-Pad40)") (class "Default")
      (node (ref "J1") (pin "40") (pinfunction "40_40") (pintype "passive"))
    )
    (net (code "78") (name "unconnected-(RJ452-NC-PadR7)") (class "Default")
      (node (ref "RJ452") (pin "R7") (pinfunction "NC_R7") (pintype "passive+no_connect"))
    )
    (net (code "79") (name "unconnected-(U2-DNC-Pad7)") (class "Default")
      (node (ref "U2") (pin "7") (pinfunction "DNC_7") (pintype "passive+no_connect"))
    )
    (net (code "80") (name "unconnected-(U2-DUPLED-Pad26)") (class "Default")
      (node (ref "U2") (pin "26") (pinfunction "DUPLED_26") (pintype "passive+no_connect"))
    )
    (net (code "81") (name "unconnected-(U2-NC-Pad12)") (class "Default")
      (node (ref "U2") (pin "12") (pinfunction "NC_12") (pintype "passive+no_connect"))
    )
    (net (code "82") (name "unconnected-(U2-NC-Pad13)") (class "Default")
      (node (ref "U2") (pin "13") (pinfunction "NC_13") (pintype "passive+no_connect"))
    )
    (net (code "83") (name "unconnected-(U2-NC-Pad46)") (class "Default")
      (node (ref "U2") (pin "46") (pinfunction "NC_46") (pintype "passive+no_connect"))
    )
    (net (code "84") (name "unconnected-(U2-NC-Pad47)") (class "Default")
      (node (ref "U2") (pin "47") (pinfunction "NC_47") (pintype "passive+no_connect"))
    )
    (net (code "85") (name "unconnected-(U2-SPDLED-Pad24)") (class "Default")
      (node (ref "U2") (pin "24") (pinfunction "SPDLED_24") (pintype "passive+no_connect"))
    )
    (net (code "86") (name "unconnected-(U2-VBG-Pad18)") (class "Default")
      (node (ref "U2") (pin "18") (pinfunction "VBG_18") (pintype "passive+no_connect"))
    )
    (net (code "87") (name "unconnected-(U3A-PA0-WKUP-Pad14)") (class "Default")
      (node (ref "U3") (pin "14") (pinfunction "PA0-WKUP_14") (pintype "bidirectional"))
    )
    (net (code "88") (name "unconnected-(U3A-PA1-Pad15)") (class "Default")
      (node (ref "U3") (pin "15") (pinfunction "PA1_15") (pintype "bidirectional"))
    )
    (net (code "89") (name "unconnected-(U3A-PA4-Pad20)") (class "Default")
      (node (ref "U3") (pin "20") (pinfunction "PA4_20") (pintype "bidirectional"))
    )
    (net (code "90") (name "unconnected-(U3A-PA5-Pad21)") (class "Default")
      (node (ref "U3") (pin "21") (pinfunction "PA5_21") (pintype "bidirectional"))
    )
    (net (code "91") (name "unconnected-(U3A-PA6-Pad22)") (class "Default")
      (node (ref "U3") (pin "22") (pinfunction "PA6_22") (pintype "bidirectional"))
    )
    (net (code "92") (name "unconnected-(U3A-PA7-Pad23)") (class "Default")
      (node (ref "U3") (pin "23") (pinfunction "PA7_23") (pintype "bidirectional"))
    )
    (net (code "93") (name "unconnected-(U3A-PA8-Pad41)") (class "Default")
      (node (ref "U3") (pin "41") (pinfunction "PA8_41") (pintype "bidirectional"))
    )
    (net (code "94") (name "unconnected-(U3A-PA12-Pad45)") (class "Default")
      (node (ref "U3") (pin "45") (pinfunction "PA12_45") (pintype "bidirectional"))
    )
    (net (code "95") (name "unconnected-(U3A-PA15-Pad50)") (class "Default")
      (node (ref "U3") (pin "50") (pinfunction "PA15_50") (pintype "bidirectional"))
    )
    (net (code "96") (name "unconnected-(U3A-PB2-Pad28)") (class "Default")
      (node (ref "U3") (pin "28") (pinfunction "PB2_28") (pintype "bidirectional"))
    )
    (net (code "97") (name "unconnected-(U3A-PB3-Pad55)") (class "Default")
      (node (ref "U3") (pin "55") (pinfunction "PB3_55") (pintype "bidirectional"))
    )
    (net (code "98") (name "unconnected-(U3A-PB4-Pad56)") (class "Default")
      (node (ref "U3") (pin "56") (pinfunction "PB4_56") (pintype "bidirectional"))
    )
    (net (code "99") (name "unconnected-(U3A-PB5-Pad57)") (class "Default")
      (node (ref "U3") (pin "57") (pinfunction "PB5_57") (pintype "bidirectional"))
    )
    (net (code "100") (name "unconnected-(U3A-PB6-Pad58)") (class "Default")
      (node (ref "U3") (pin "58") (pinfunction "PB6_58") (pintype "bidirectional"))
    )
    (net (code "101") (name "unconnected-(U3A-PB7-Pad59)") (class "Default")
      (node (ref "U3") (pin "59") (pinfunction "PB7_59") (pintype "bidirectional"))
    )
    (net (code "102") (name "unconnected-(U3A-PB8-Pad61)") (class "Default")
      (node (ref "U3") (pin "61") (pinfunction "PB8_61") (pintype "bidirectional"))
    )
    (net (code "103") (name "unconnected-(U3A-PB9-Pad62)") (class "Default")
      (node (ref "U3") (pin "62") (pinfunction "PB9_62") (pintype "bidirectional"))
    )
    (net (code "104") (name "unconnected-(U3A-PB10-Pad29)") (class "Default")
      (node (ref "U3") (pin "29") (pinfunction "PB10_29") (pintype "bidirectional"))
    )
    (net (code "105") (name "unconnected-(U3A-PB11-Pad30)") (class "Default")
      (node (ref "U3") (pin "30") (pinfunction "PB11_30") (pintype "bidirectional"))
    )
    (net (code "106") (name "unconnected-(U3A-PC2-Pad10)") (class "Default")
      (node (ref "U3") (pin "10") (pinfunction "PC2_10") (pintype "bidirectional"))
    )
    (net (code "107") (name "unconnected-(U3A-PC3-Pad11)") (class "Default")
      (node (ref "U3") (pin "11") (pinfunction "PC3_11") (pintype "bidirectional"))
    )
    (net (code "108") (name "unconnected-(U3A-PC9-Pad40)") (class "Default")
      (node (ref "U3") (pin "40") (pinfunction "PC9_40") (pintype "bidirectional"))
    )
    (net (code "109") (name "unconnected-(U3A-PC10-Pad51)") (class "Default")
      (node (ref "U3") (pin "51") (pinfunction "PC10_51") (pintype "bidirectional"))
    )
    (net (code "110") (name "unconnected-(U3A-PC13-TAMPER-RTC-Pad2)") (class "Default")
      (node (ref "U3") (pin "2") (pinfunction "PC13-TAMPER-RTC_2") (pintype "bidirectional"))
    )
    (net (code "111") (name "unconnected-(U3A-PC14-OSC32_IN-Pad3)") (class "Default")
      (node (ref "U3") (pin "3") (pinfunction "PC14-OSC32_IN_3") (pintype "bidirectional"))
    )
    (net (code "112") (name "unconnected-(U3A-PC15-OSC32_OUT-Pad4)") (class "Default")
      (node (ref "U3") (pin "4") (pinfunction "PC15-OSC32_OUT_4") (pintype "bidirectional"))
    )
    (net (code "113") (name "unconnected-(U3A-PD2-Pad54)") (class "Default")
      (node (ref "U3") (pin "54") (pinfunction "PD2_54") (pintype "bidirectional"))
    )
    (net (code "114") (name "unconnected-(U3B-VBAT-Pad1)") (class "Default")
      (node (ref "U3") (pin "1") (pinfunction "VBAT_1") (pintype "power_in"))
    )
  )
)
